# Slave_Schematic.net
KiCad netlist of a schematic drawn in EAGLE
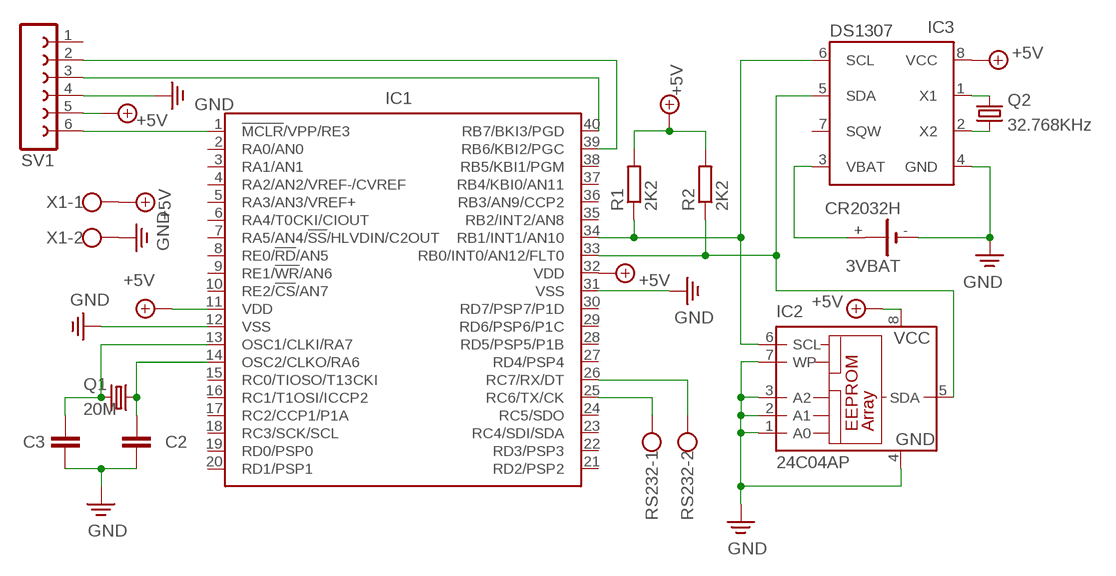
[diagram p0: schematic, sheet 1]

(export (version "E")
  (design (tool "Eeschema 10.0.6"))
  (components
    (comp (ref "3VBAT")
      (value "CR2032H")
      (footprint "eagle-import:CR2032H")
      (libsource (lib "eagle-import") (part "CR2032H"))
    )
    (comp (ref "C2")
      (value "C-EU025-025X050")
      (footprint "eagle-import:C025-025X050")
      (libsource (lib "eagle-import") (part "C-EU025-025X050"))
    )
    (comp (ref "C3")
      (value "C-EU025-025X050")
      (footprint "eagle-import:C025-025X050")
      (libsource (lib "eagle-import") (part "C-EU025-025X050"))
    )
    (comp (ref "IC1")
      (value "PIC18F4620")
      (footprint "eagle-import:DIL40")
      (libsource (lib "eagle-import") (part "PIC18F4620"))
    )
    (comp (ref "IC2")
      (value "24C04AP")
      (footprint "eagle-import:DIL8")
      (fields (field (name "MF") "RAMTRON INTERNATIONAL CORP") (field (name "MPN") "FM24C04A-P"))
      (libsource (lib "eagle-import") (part "24PC04A"))
    )
    (comp (ref "IC3")
      (value "DS1307")
      (footprint "eagle-import:DIL08")
      (libsource (lib "eagle-import") (part "DS1307"))
    )
    (comp (ref "Q1")
      (value "20M")
      (footprint "eagle-import:HC49_S")
      (libsource (lib "eagle-import") (part "CRYSTALHC49S"))
    )
    (comp (ref "Q2")
      (value "32.768KHz")
      (footprint "eagle-import:HC49_S")
      (libsource (lib "eagle-import") (part "CRYSTALHC49S"))
    )
    (comp (ref "R1")
      (value "2K2")
      (footprint "eagle-import:0207_7")
      (libsource (lib "eagle-import") (part "R-EU_0207/7"))
    )
    (comp (ref "R2")
      (value "2K2")
      (footprint "eagle-import:0207_7")
      (libsource (lib "eagle-import") (part "R-EU_0207/7"))
    )
    (comp (ref "RS232")
      (value "W237-102")
      (footprint "eagle-import:W237-102")
      (fields (field (name "MPN") "237-102"))
      (libsource (lib "eagle-import") (part "W237-102"))
    )
    (comp (ref "SV1")
      (value "FE06-1")
      (footprint "eagle-import:FE06")
      (libsource (lib "eagle-import") (part "FE06-1"))
    )
    (comp (ref "X1")
      (value "W237-102")
      (footprint "eagle-import:W237-102")
      (fields (field (name "MPN") "237-102"))
      (libsource (lib "eagle-import") (part "W237-102"))
    )
  )
  (nets
    (net (code "1") (name "+5V") (class "Default")
      (node (ref "IC1") (pin "11") (pinfunction "VDD_11") (pintype "power_in"))
      (node (ref "IC1") (pin "32") (pinfunction "VDD_32") (pintype "power_in"))
      (node (ref "IC2") (pin "8") (pinfunction "VCC_8") (pintype "power_in"))
      (node (ref "IC3") (pin "8") (pinfunction "VCC_8") (pintype "power_in"))
      (node (ref "R1") (pin "2") (pinfunction "2_2") (pintype "passive"))
      (node (ref "R2") (pin "2") (pinfunction "2_2") (pintype "passive"))
      (node (ref "SV1") (pin "5") (pinfunction "5_5") (pintype "passive"))
      (node (ref "X1") (pin "1") (pinfunction "KL_1") (pintype "passive"))
    )
    (net (code "2") (name "GND") (class "Default")
      (node (ref "3VBAT") (pin "-") (pinfunction "-_-") (pintype "passive"))
      (node (ref "C2") (pin "2") (pinfunction "2_2") (pintype "passive"))
      (node (ref "C3") (pin "1") (pinfunction "1_1") (pintype "passive"))
      (node (ref "IC1") (pin "12") (pinfunction "VSS_12") (pintype "power_in"))
      (node (ref "IC1") (pin "31") (pinfunction "VSS_31") (pintype "power_in"))
      (node (ref "IC2") (pin "1") (pinfunction "A0_1") (pintype "input"))
      (node (ref "IC2") (pin "2") (pinfunction "A1_2") (pintype "input"))
      (node (ref "IC2") (pin "3") (pinfunction "A2_3") (pintype "input"))
      (node (ref "IC2") (pin "4") (pinfunction "GND_4") (pintype "power_in"))
      (node (ref "IC2") (pin "7") (pinfunction "WP_7") (pintype "input"))
      (node (ref "IC3") (pin "4") (pinfunction "GND_4") (pintype "power_in"))
      (node (ref "SV1") (pin "4") (pinfunction "4_4") (pintype "passive"))
      (node (ref "X1") (pin "2") (pinfunction "KL_2") (pintype "passive"))
    )
    (net (code "3") (name "Net-(IC1-OSC1{slash}CLKI{slash}RA7)") (class "Default")
      (node (ref "C3") (pin "2") (pinfunction "2_2") (pintype "passive"))
      (node (ref "IC1") (pin "13") (pinfunction "OSC1/CLKI/RA7_13") (pintype "input"))
      (node (ref "Q1") (pin "2") (pinfunction "2_2") (pintype "passive"))
    )
    (net (code "4") (name "Net-(IC1-OSC2{slash}CLKO{slash}RA6)") (class "Default")
      (node (ref "C2") (pin "1") (pinfunction "1_1") (pintype "passive"))
      (node (ref "IC1") (pin "14") (pinfunction "OSC2/CLKO/RA6_14") (pintype "output"))
      (node (ref "Q1") (pin "1") (pinfunction "1_1") (pintype "passive"))
    )
    (net (code "5") (name "Net-(IC1-RB0{slash}INT0{slash}AN12{slash}FLT0)") (class "Default")
      (node (ref "IC1") (pin "33") (pinfunction "RB0/INT0/AN12/FLT0_33") (pintype "bidirectional"))
      (node (ref "IC2") (pin "5") (pinfunction "SDA_5") (pintype "bidirectional"))
      (node (ref "IC3") (pin "5") (pinfunction "SDA_5") (pintype "bidirectional"))
      (node (ref "R2") (pin "1") (pinfunction "1_1") (pintype "passive"))
    )
    (net (code "6") (name "Net-(IC1-RB1{slash}INT1{slash}AN10)") (class "Default")
      (node (ref "IC1") (pin "34") (pinfunction "RB1/INT1/AN10_34") (pintype "bidirectional"))
      (node (ref "IC2") (pin "6") (pinfunction "SCL_6") (pintype "input"))
      (node (ref "IC3") (pin "6") (pinfunction "SCL_6") (pintype "input"))
      (node (ref "R1") (pin "1") (pinfunction "1_1") (pintype "passive"))
    )
    (net (code "7") (name "Net-(IC1-RB6{slash}KBI2{slash}PGC)") (class "Default")
      (node (ref "IC1") (pin "39") (pinfunction "RB6/KBI2/PGC_39") (pintype "bidirectional"))
      (node (ref "SV1") (pin "2") (pinfunction "2_2") (pintype "passive"))
    )
    (net (code "8") (name "Net-(IC1-RB7{slash}BKI3{slash}PGD)") (class "Default")
      (node (ref "IC1") (pin "40") (pinfunction "RB7/BKI3/PGD_40") (pintype "bidirectional"))
      (node (ref "SV1") (pin "3") (pinfunction "3_3") (pintype "passive"))
    )
    (net (code "9") (name "Net-(IC1-RC6{slash}TX{slash}CK)") (class "Default")
      (node (ref "IC1") (pin "25") (pinfunction "RC6/TX/CK_25") (pintype "bidirectional"))
      (node (ref "RS232") (pin "1") (pinfunction "KL_1") (pintype "passive"))
    )
    (net (code "10") (name "Net-(IC1-RC7{slash}RX{slash}DT)") (class "Default")
      (node (ref "IC1") (pin "26") (pinfunction "RC7/RX/DT_26") (pintype "bidirectional"))
      (node (ref "RS232") (pin "2") (pinfunction "KL_2") (pintype "passive"))
    )
    (net (code "11") (name "Net-(IC1-~{MCLR}{slash}VPP{slash}RE3)") (class "Default")
      (node (ref "IC1") (pin "1") (pinfunction "~{MCLR}/VPP/RE3_1") (pintype "input"))
      (node (ref "SV1") (pin "6") (pinfunction "6_6") (pintype "passive"))
    )
    (net (code "12") (name "Net-(IC3-VBAT)") (class "Default")
      (node (ref "3VBAT") (pin "+") (pinfunction "+_+") (pintype "passive"))
      (node (ref "IC3") (pin "3") (pinfunction "VBAT_3") (pintype "passive"))
    )
    (net (code "13") (name "Net-(IC3-X1)") (class "Default")
      (node (ref "IC3") (pin "1") (pinfunction "X1_1") (pintype "input"))
      (node (ref "Q2") (pin "2") (pinfunction "2_2") (pintype "passive"))
    )
    (net (code "14") (name "Net-(IC3-X2)") (class "Default")
      (node (ref "IC3") (pin "2") (pinfunction "X2_2") (pintype "output"))
      (node (ref "Q2") (pin "1") (pinfunction "1_1") (pintype "passive"))
    )
    (net (code "15") (name "unconnected-(3VBAT-+-Pad+@1)") (class "Default")
      (node (ref "3VBAT") (pin "+@1") (pinfunction "+_+@1") (pintype "passive"))
    )
    (net (code "16") (name "unconnected-(IC1-RA0{slash}AN0-Pad2)") (class "Default")
      (node (ref "IC1") (pin "2") (pinfunction "RA0/AN0_2") (pintype "bidirectional"))
    )
    (net (code "17") (name "unconnected-(IC1-RA1{slash}AN1-Pad3)") (class "Default")
      (node (ref "IC1") (pin "3") (pinfunction "RA1/AN1_3") (pintype "bidirectional"))
    )
    (net (code "18") (name "unconnected-(IC1-RA2{slash}AN2{slash}VREF-{slash}CVREF-Pad4)") (class "Default")
      (node (ref "IC1") (pin "4") (pinfunction "RA2/AN2/VREF-/CVREF_4") (pintype "bidirectional"))
    )
    (net (code "19") (name "unconnected-(IC1-RA3{slash}AN3{slash}VREF+-Pad5)") (class "Default")
      (node (ref "IC1") (pin "5") (pinfunction "RA3/AN3/VREF+_5") (pintype "bidirectional"))
    )
    (net (code "20") (name "unconnected-(IC1-RA4{slash}T0CKI{slash}CIOUT-Pad6)") (class "Default")
      (node (ref "IC1") (pin "6") (pinfunction "RA4/T0CKI/CIOUT_6") (pintype "bidirectional"))
    )
    (net (code "21") (name "unconnected-(IC1-RA5{slash}AN4{slash}~{SS}{slash}HLVDIN{slash}C2OUT-Pad7)") (class "Default")
      (node (ref "IC1") (pin "7") (pinfunction "RA5/AN4/~{SS}/HLVDIN/C2OUT_7") (pintype "bidirectional"))
    )
    (net (code "22") (name "unconnected-(IC1-RB2{slash}INT2{slash}AN8-Pad35)") (class "Default")
      (node (ref "IC1") (pin "35") (pinfunction "RB2/INT2/AN8_35") (pintype "bidirectional"))
    )
    (net (code "23") (name "unconnected-(IC1-RB3{slash}AN9{slash}CCP2-Pad36)") (class "Default")
      (node (ref "IC1") (pin "36") (pinfunction "RB3/AN9/CCP2_36") (pintype "bidirectional"))
    )
    (net (code "24") (name "unconnected-(IC1-RB4{slash}KBI0{slash}AN11-Pad37)") (class "Default")
      (node (ref "IC1") (pin "37") (pinfunction "RB4/KBI0/AN11_37") (pintype "bidirectional"))
    )
    (net (code "25") (name "unconnected-(IC1-RB5{slash}KBI1{slash}PGM-Pad38)") (class "Default")
      (node (ref "IC1") (pin "38") (pinfunction "RB5/KBI1/PGM_38") (pintype "bidirectional"))
    )
    (net (code "26") (name "unconnected-(IC1-RC0{slash}TIOSO{slash}T13CKI-Pad15)") (class "Default")
      (node (ref "IC1") (pin "15") (pinfunction "RC0/TIOSO/T13CKI_15") (pintype "bidirectional"))
    )
    (net (code "27") (name "unconnected-(IC1-RC1{slash}T1OSI{slash}ICCP2-Pad16)") (class "Default")
      (node (ref "IC1") (pin "16") (pinfunction "RC1/T1OSI/ICCP2_16") (pintype "bidirectional"))
    )
    (net (code "28") (name "unconnected-(IC1-RC2{slash}CCP1{slash}P1A-Pad17)") (class "Default")
      (node (ref "IC1") (pin "17") (pinfunction "RC2/CCP1/P1A_17") (pintype "bidirectional"))
    )
    (net (code "29") (name "unconnected-(IC1-RC3{slash}SCK{slash}SCL-Pad18)") (class "Default")
      (node (ref "IC1") (pin "18") (pinfunction "RC3/SCK/SCL_18") (pintype "bidirectional"))
    )
    (net (code "30") (name "unconnected-(IC1-RC4{slash}SDI{slash}SDA-Pad23)") (class "Default")
      (node (ref "IC1") (pin "23") (pinfunction "RC4/SDI/SDA_23") (pintype "bidirectional"))
    )
    (net (code "31") (name "unconnected-(IC1-RC5{slash}SDO-Pad24)") (class "Default")
      (node (ref "IC1") (pin "24") (pinfunction "RC5/SDO_24") (pintype "bidirectional"))
    )
    (net (code "32") (name "unconnected-(IC1-RD0{slash}PSP0-Pad19)") (class "Default")
      (node (ref "IC1") (pin "19") (pinfunction "RD0/PSP0_19") (pintype "bidirectional"))
    )
    (net (code "33") (name "unconnected-(IC1-RD1{slash}PSP1-Pad20)") (class "Default")
      (node (ref "IC1") (pin "20") (pinfunction "RD1/PSP1_20") (pintype "bidirectional"))
    )
    (net (code "34") (name "unconnected-(IC1-RD2{slash}PSP2-Pad21)") (class "Default")
      (node (ref "IC1") (pin "21") (pinfunction "RD2/PSP2_21") (pintype "bidirectional"))
    )
    (net (code "35") (name "unconnected-(IC1-RD3{slash}PSP3-Pad22)") (class "Default")
      (node (ref "IC1") (pin "22") (pinfunction "RD3/PSP3_22") (pintype "bidirectional"))
    )
    (net (code "36") (name "unconnected-(IC1-RD4{slash}PSP4-Pad27)") (class "Default")
      (node (ref "IC1") (pin "27") (pinfunction "RD4/PSP4_27") (pintype "bidirectional"))
    )
    (net (code "37") (name "unconnected-(IC1-RD5{slash}PSP5{slash}P1B-Pad28)") (class "Default")
      (node (ref "IC1") (pin "28") (pinfunction "RD5/PSP5/P1B_28") (pintype "bidirectional"))
    )
    (net (code "38") (name "unconnected-(IC1-RD6{slash}PSP6{slash}P1C-Pad29)") (class "Default")
      (node (ref "IC1") (pin "29") (pinfunction "RD6/PSP6/P1C_29") (pintype "bidirectional"))
    )
    (net (code "39") (name "unconnected-(IC1-RD7{slash}PSP7{slash}P1D-Pad30)") (class "Default")
      (node (ref "IC1") (pin "30") (pinfunction "RD7/PSP7/P1D_30") (pintype "bidirectional"))
    )
    (net (code "40") (name "unconnected-(IC1-RE0{slash}~{RD}{slash}AN5-Pad8)") (class "Default")
      (node (ref "IC1") (pin "8") (pinfunction "RE0/~{RD}/AN5_8") (pintype "bidirectional"))
    )
    (net (code "41") (name "unconnected-(IC1-RE1{slash}~{WR}{slash}AN6-Pad9)") (class "Default")
      (node (ref "IC1") (pin "9") (pinfunction "RE1/~{WR}/AN6_9") (pintype "bidirectional"))
    )
    (net (code "42") (name "unconnected-(IC1-RE2{slash}~{CS}{slash}AN7-Pad10)") (class "Default")
      (node (ref "IC1") (pin "10") (pinfunction "RE2/~{CS}/AN7_10") (pintype "bidirectional"))
    )
    (net (code "43") (name "unconnected-(IC3-SQW-Pad7)") (class "Default")
      (node (ref "IC3") (pin "7") (pinfunction "SQW_7") (pintype "open_collector"))
    )
    (net (code "44") (name "unconnected-(SV1-Pad1)") (class "Default")
      (node (ref "SV1") (pin "1") (pinfunction "1_1") (pintype "passive"))
    )
  )
)
